# Etapa_Potencia.net
KiCad netlist of a schematic drawn in Altium Designer
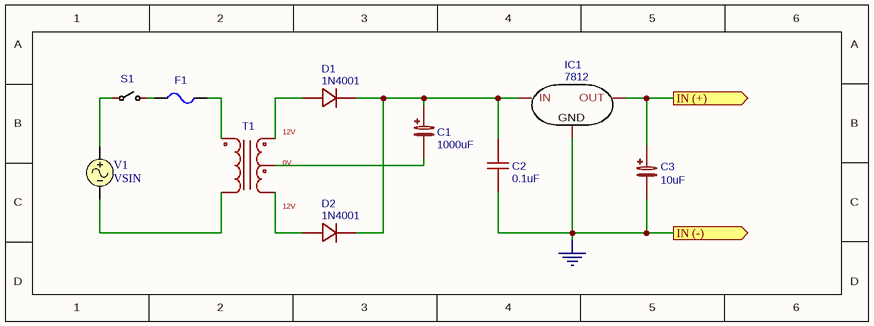
[diagram p0: Etapa_Potencia.schdoc]

(export (version "E")
  (design (tool "Eeschema 10.0.6"))
  (components
    (comp (ref "C1")
      (value "1000uF")
      (footprint "CAP-D3.0XF1.5")
      (fields (field (name "BOM_MANUFACTURER PART") "?"))
      (libsource (lib "altium-import") (part "root_0_1000uF_"))
    )
    (comp (ref "C2")
      (value "0.1uF")
      (footprint "RAD-0.1")
      (fields (field (name "BOM_MANUFACTURER PART") "?"))
      (libsource (lib "altium-import") (part "root_0_0.1uF_"))
    )
    (comp (ref "C3")
      (value "10uF")
      (footprint "CAP-D3.0XF1.5")
      (fields (field (name "BOM_MANUFACTURER PART") "?"))
      (libsource (lib "altium-import") (part "root_0_10uF_"))
    )
    (comp (ref "D1")
      (value "1N4001")
      (footprint "DO35-10")
      (fields (field (name "BOM_MANUFACTURER PART") "?"))
      (libsource (lib "altium-import") (part "root_0_1N4001_"))
    )
    (comp (ref "D2")
      (value "1N4001")
      (footprint "DO35-10")
      (fields (field (name "BOM_MANUFACTURER PART") "?"))
      (libsource (lib "altium-import") (part "root_0_1N4001_"))
    )
    (comp (ref "F1")
      (value "FUSE")
      (footprint "FUSE3.15A")
      (fields (field (name "BOM_MANUFACTURER PART") "?"))
      (libsource (lib "altium-import") (part "root_0_FUSE_"))
    )
    (comp (ref "IC1")
      (value "7812")
      (footprint "TO92")
      (fields (field (name "BOM_MANUFACTURER PART") "?") (field (name "CONTRIBUTOR") "Chayapol"))
      (libsource (lib "altium-import") (part "root_0_7812_"))
    )
    (comp (ref "S1")
      (value "DUAL_SWITCH_INV")
      (footprint "NONE")
      (fields (field (name "BOM_MANUFACTURER PART") "?") (field (name "CONTRIBUTOR") "KiCad"))
      (libsource (lib "altium-import") (part "root_0_DUAL_SWITCH_INV_"))
    )
    (comp (ref "T1")
      (value "XFMR_TAP")
      (footprint "TRANSFORMER 2 TO 3")
      (fields (field (name "BOM_MANUFACTURER PART") "?"))
      (libsource (lib "altium-import") (part "root_0_XFMR_TAP_"))
    )
    (comp (ref "V1")
      (value "VSIN")
      (description "Sinusoidal Voltage Source")
      (fields (field (name "PUBLISHER") "Altium Limited"))
      (libsource (lib "Simulation Sources") (part "VSIN"))
    )
  )
  (nets
    (net (code "1") (name "/IN (+)") (class "Default")
      (node (ref "C3") (pin "1") (pinfunction "1_1") (pintype "passive"))
      (node (ref "IC1") (pin "1") (pinfunction "OUT_1") (pintype "passive"))
    )
    (net (code "2") (name "GND") (class "Default")
      (node (ref "C2") (pin "1") (pinfunction "1_1") (pintype "passive"))
      (node (ref "C3") (pin "2") (pinfunction "2_2") (pintype "passive"))
      (node (ref "IC1") (pin "2") (pinfunction "GND_2") (pintype "passive"))
    )
    (net (code "3") (name "Net-(C1-Pad2)") (class "Default")
      (node (ref "C1") (pin "2") (pinfunction "2_2") (pintype "passive"))
      (node (ref "T1") (pin "4") (pinfunction "4_4") (pintype "passive"))
    )
    (net (code "4") (name "Net-(D1-+)") (class "Default")
      (node (ref "D1") (pin "1") (pinfunction "+_1") (pintype "passive"))
      (node (ref "T1") (pin "5") (pinfunction "5_5") (pintype "passive"))
    )
    (net (code "5") (name "Net-(D1--)") (class "Default")
      (node (ref "C1") (pin "1") (pinfunction "1_1") (pintype "passive"))
      (node (ref "C2") (pin "2") (pinfunction "2_2") (pintype "passive"))
      (node (ref "D1") (pin "2") (pinfunction "-_2") (pintype "passive"))
      (node (ref "D2") (pin "2") (pinfunction "-_2") (pintype "passive"))
      (node (ref "IC1") (pin "3") (pinfunction "IN_3") (pintype "passive"))
    )
    (net (code "6") (name "Net-(D2-+)") (class "Default")
      (node (ref "D2") (pin "1") (pinfunction "+_1") (pintype "passive"))
      (node (ref "T1") (pin "3") (pinfunction "3_3") (pintype "passive"))
    )
    (net (code "7") (name "Net-(F1-A-Pad1)") (class "Default")
      (node (ref "F1") (pin "1") (pinfunction "A_1") (pintype "passive"))
      (node (ref "S1") (pin "1") (pinfunction "1_1") (pintype "passive"))
    )
    (net (code "8") (name "Net-(F1-A-Pad2)") (class "Default")
      (node (ref "F1") (pin "2") (pinfunction "A_2") (pintype "passive"))
      (node (ref "T1") (pin "1") (pinfunction "1_1") (pintype "passive"))
    )
    (net (code "9") (name "Net-(S1-Pad2)") (class "Default")
      (node (ref "S1") (pin "2") (pinfunction "2_2") (pintype "passive"))
      (node (ref "V1") (pin "1") (pinfunction "1_1") (pintype "passive"))
    )
    (net (code "10") (name "Net-(T1-Pad2)") (class "Default")
      (node (ref "T1") (pin "2") (pinfunction "2_2") (pintype "passive"))
      (node (ref "V1") (pin "2") (pinfunction "2_2") (pintype "passive"))
    )
  )
)
